# Pi3-Motherboard.net
KiCad netlist of a schematic drawn in EAGLE
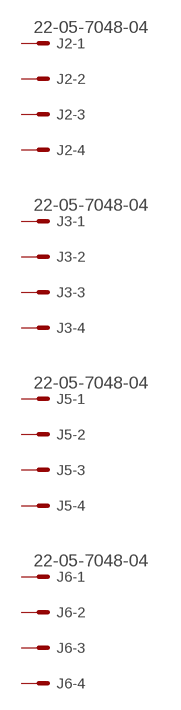
[diagram p0: schematic, sheet 1]
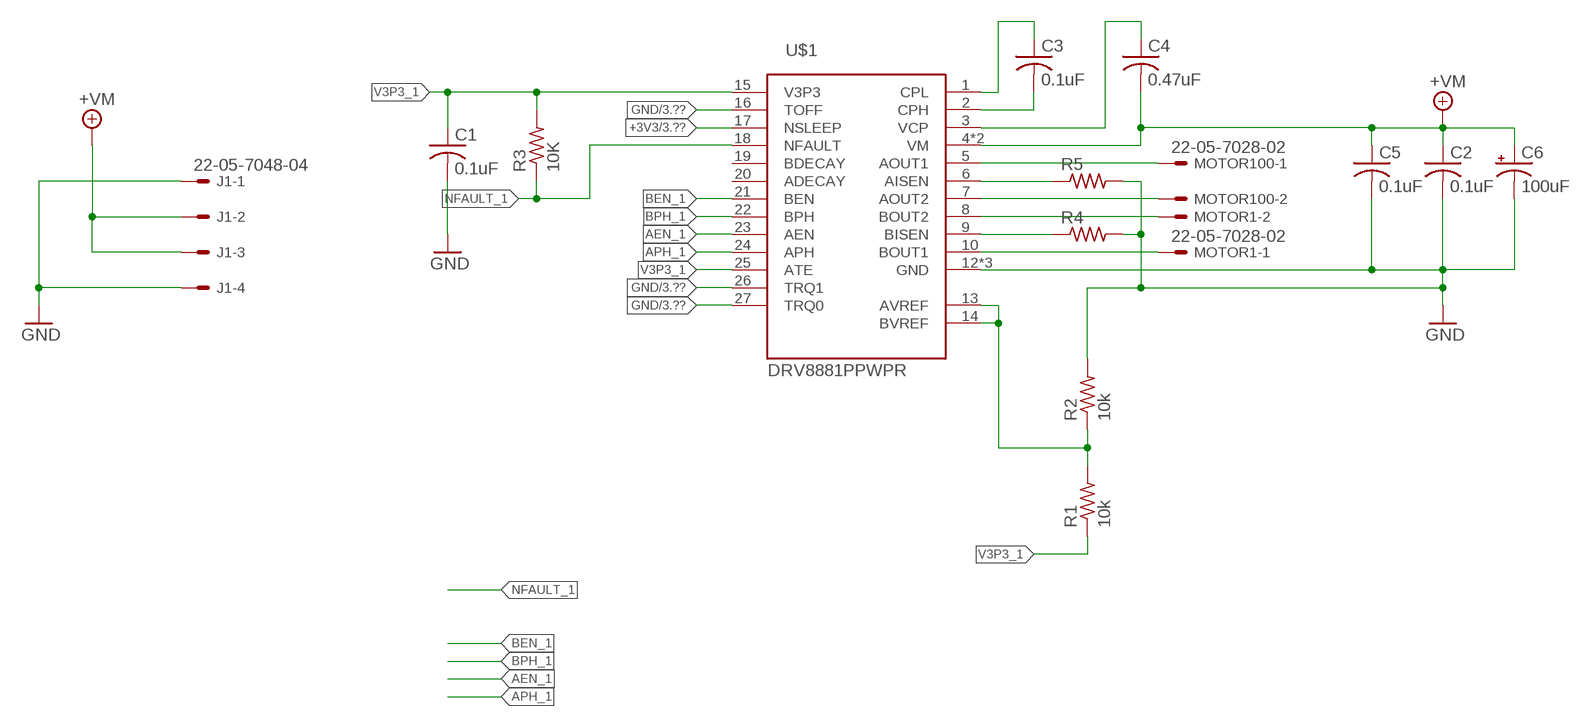
[diagram p1: schematic, sheet 2]
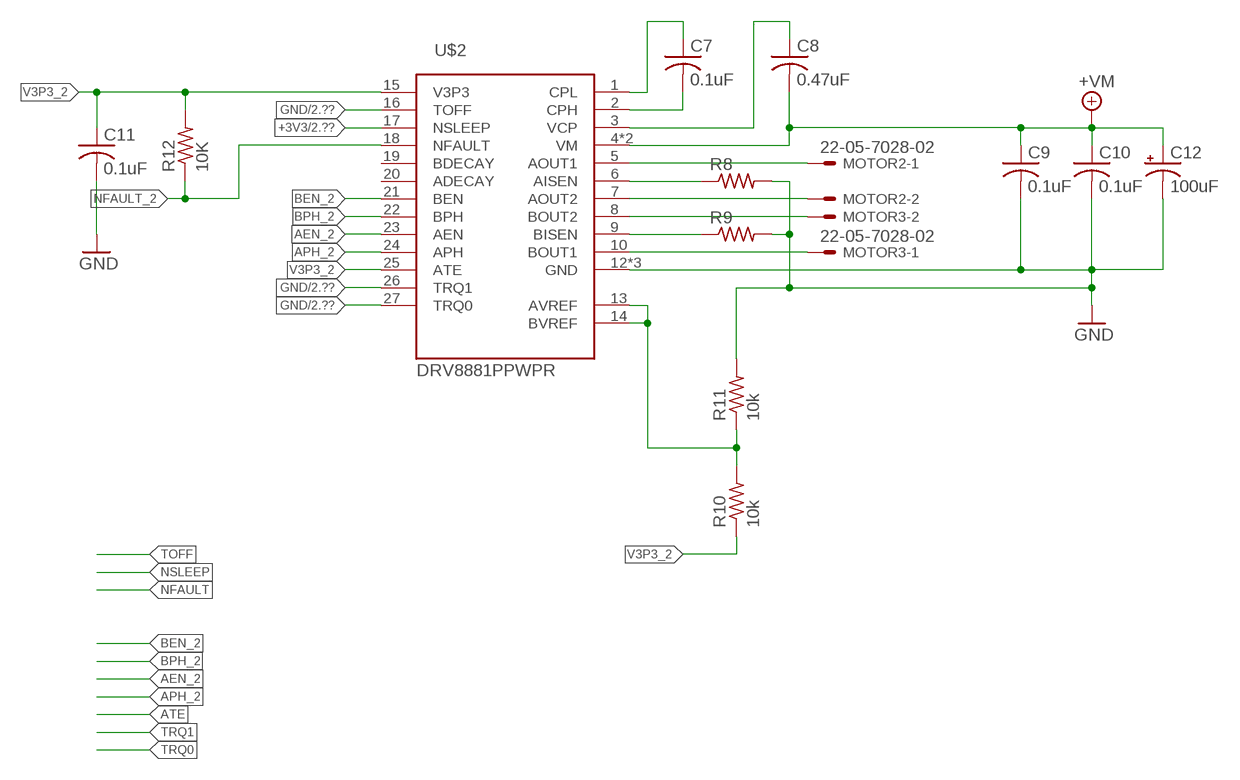
[diagram p2: schematic, sheet 3]
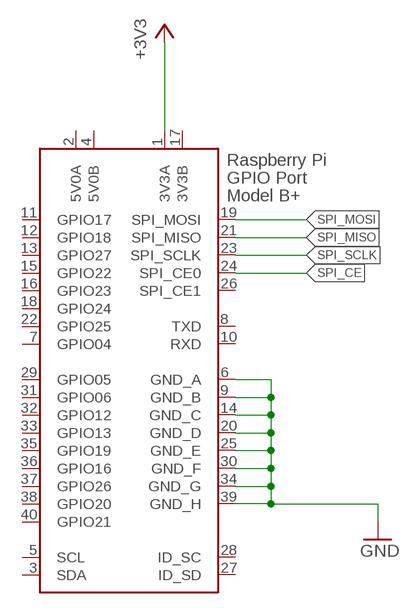
[diagram p3: schematic, sheet 4]
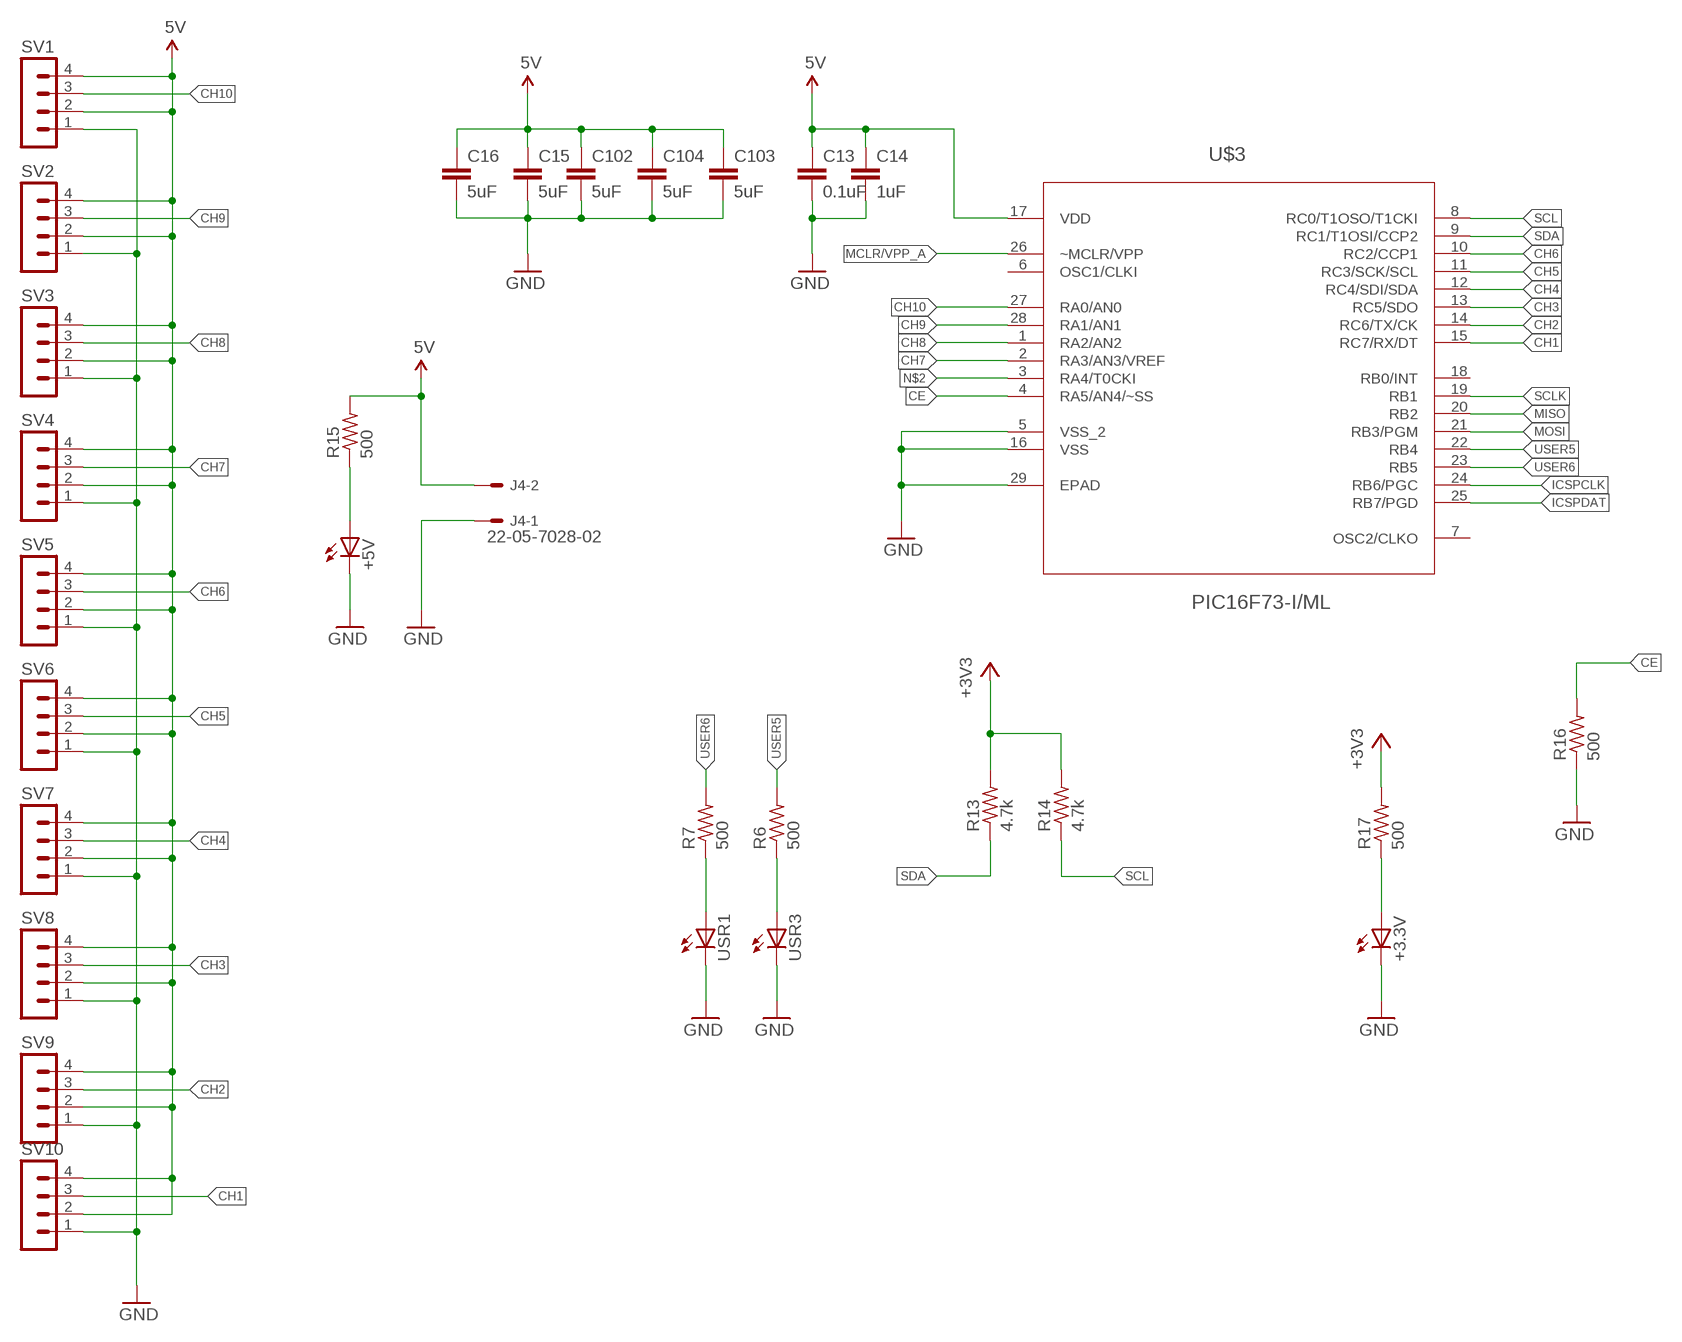
[diagram p4: schematic, sheet 5]

(export (version "E")
  (design (tool "Eeschema 10.0.6"))
  (components
    (comp (ref "X1")
      (value "RASPI_BOARD_B+#_HD")
      (footprint "eagle-import:RASPI_BOARD_B+HAT_DF")
      (libsource (lib "eagle-import") (part "RASPI_BOARD_B+#_HD"))
    )
    (comp (ref "+3.3V")
      (value "LEDCHIP-LED0603")
      (footprint "eagle-import:CHIP-LED0603")
      (libsource (lib "eagle-import") (part "LEDCHIP-LED0603"))
    )
    (comp (ref "+5V")
      (value "LEDCHIP-LED0603")
      (footprint "eagle-import:CHIP-LED0603")
      (libsource (lib "eagle-import") (part "LEDCHIP-LED0603"))
    )
    (comp (ref "C13")
      (value "0.1uF")
      (footprint "eagle-import:C0402")
      (libsource (lib "eagle-import") (part "C-EUC0402"))
    )
    (comp (ref "C14")
      (value "1uF")
      (footprint "eagle-import:C0402")
      (libsource (lib "eagle-import") (part "C-EUC0402"))
    )
    (comp (ref "C15")
      (value "5uF")
      (footprint "eagle-import:C0402")
      (libsource (lib "eagle-import") (part "C-EUC0402"))
    )
    (comp (ref "C16")
      (value "5uF")
      (footprint "eagle-import:C0402")
      (libsource (lib "eagle-import") (part "C-EUC0402"))
    )
    (comp (ref "C102")
      (value "5uF")
      (footprint "eagle-import:C0402")
      (libsource (lib "eagle-import") (part "C-EUC0402"))
    )
    (comp (ref "C103")
      (value "5uF")
      (footprint "eagle-import:C0402")
      (libsource (lib "eagle-import") (part "C-EUC0402"))
    )
    (comp (ref "C104")
      (value "5uF")
      (footprint "eagle-import:C0402")
      (libsource (lib "eagle-import") (part "C-EUC0402"))
    )
    (comp (ref "J4")
      (value "22-05-7028-02")
      (footprint "eagle-import:7395-02")
      (libsource (lib "eagle-import") (part "con-molex_22-?-0205-7028"))
    )
    (comp (ref "R6")
      (value "500")
      (footprint "eagle-import:R0402")
      (libsource (lib "eagle-import") (part "resistor_R-US_R0402"))
    )
    (comp (ref "R7")
      (value "500")
      (footprint "eagle-import:R0402")
      (libsource (lib "eagle-import") (part "resistor_R-US_R0402"))
    )
    (comp (ref "R13")
      (value "4.7k")
      (footprint "eagle-import:R0402")
      (libsource (lib "eagle-import") (part "resistor_R-US_R0402"))
    )
    (comp (ref "R14")
      (value "4.7k")
      (footprint "eagle-import:R0402")
      (libsource (lib "eagle-import") (part "resistor_R-US_R0402"))
    )
    (comp (ref "R15")
      (value "500")
      (footprint "eagle-import:R0402")
      (libsource (lib "eagle-import") (part "resistor_R-US_R0402"))
    )
    (comp (ref "R16")
      (value "500")
      (footprint "eagle-import:R0402")
      (libsource (lib "eagle-import") (part "resistor_R-US_R0402"))
    )
    (comp (ref "R17")
      (value "500")
      (footprint "eagle-import:R0402")
      (libsource (lib "eagle-import") (part "resistor_R-US_R0402"))
    )
    (comp (ref "SV1")
      (value "MA04-1")
      (footprint "eagle-import:MA04-1")
      (libsource (lib "eagle-import") (part "MA04-1"))
    )
    (comp (ref "SV2")
      (value "MA04-1")
      (footprint "eagle-import:MA04-1")
      (libsource (lib "eagle-import") (part "MA04-1"))
    )
    (comp (ref "SV3")
      (value "MA04-1")
      (footprint "eagle-import:MA04-1")
      (libsource (lib "eagle-import") (part "MA04-1"))
    )
    (comp (ref "SV4")
      (value "MA04-1")
      (footprint "eagle-import:MA04-1")
      (libsource (lib "eagle-import") (part "MA04-1"))
    )
    (comp (ref "SV5")
      (value "MA04-1")
      (footprint "eagle-import:MA04-1")
      (libsource (lib "eagle-import") (part "MA04-1"))
    )
    (comp (ref "SV6")
      (value "MA04-1")
      (footprint "eagle-import:MA04-1")
      (libsource (lib "eagle-import") (part "MA04-1"))
    )
    (comp (ref "SV7")
      (value "MA04-1")
      (footprint "eagle-import:MA04-1")
      (libsource (lib "eagle-import") (part "MA04-1"))
    )
    (comp (ref "SV8")
      (value "MA04-1")
      (footprint "eagle-import:MA04-1")
      (libsource (lib "eagle-import") (part "MA04-1"))
    )
    (comp (ref "SV9")
      (value "MA04-1")
      (footprint "eagle-import:MA04-1")
      (libsource (lib "eagle-import") (part "MA04-1"))
    )
    (comp (ref "SV10")
      (value "MA04-1")
      (footprint "eagle-import:MA04-1")
      (libsource (lib "eagle-import") (part "MA04-1"))
    )
    (comp (ref "U$3")
      (value "PIC16F73-I/ML")
      (footprint "eagle-import:QFN65P600X600X100-28N")
      (libsource (lib "eagle-import") (part "PIC16F73-I/ML"))
    )
    (comp (ref "USR1")
      (value "LEDCHIP-LED0603")
      (footprint "eagle-import:CHIP-LED0603")
      (libsource (lib "eagle-import") (part "LEDCHIP-LED0603"))
    )
    (comp (ref "USR3")
      (value "LEDCHIP-LED0603")
      (footprint "eagle-import:CHIP-LED0603")
      (libsource (lib "eagle-import") (part "LEDCHIP-LED0603"))
    )
    (comp (ref "J2")
      (value "22-05-7048-04")
      (footprint "eagle-import:7395-04")
      (libsource (lib "eagle-import") (part "22-?-0405-7048"))
    )
    (comp (ref "J3")
      (value "22-05-7048-04")
      (footprint "eagle-import:7395-04")
      (libsource (lib "eagle-import") (part "22-?-0405-7048"))
    )
    (comp (ref "J5")
      (value "22-05-7048-04")
      (footprint "eagle-import:7395-04")
      (libsource (lib "eagle-import") (part "22-?-0405-7048"))
    )
    (comp (ref "J6")
      (value "22-05-7048-04")
      (footprint "eagle-import:7395-04")
      (libsource (lib "eagle-import") (part "22-?-0405-7048"))
    )
    (comp (ref "C1")
      (value "0.1uF")
      (footprint "eagle-import:C0402")
      (libsource (lib "eagle-import") (part "C-USC0402"))
    )
    (comp (ref "C2")
      (value "0.1uF")
      (footprint "eagle-import:C0402")
      (libsource (lib "eagle-import") (part "C-USC0402"))
    )
    (comp (ref "C3")
      (value "0.1uF")
      (footprint "eagle-import:C0402")
      (libsource (lib "eagle-import") (part "C-USC0402"))
    )
    (comp (ref "C4")
      (value "0.47uF")
      (footprint "eagle-import:C0402")
      (libsource (lib "eagle-import") (part "C-USC0402"))
    )
    (comp (ref "C5")
      (value "0.1uF")
      (footprint "eagle-import:C0402")
      (libsource (lib "eagle-import") (part "C-USC0402"))
    )
    (comp (ref "C6")
      (value "100uF")
      (footprint "eagle-import:EIA7343")
      (libsource (lib "eagle-import") (part "100UF-10V-10%(TANT)"))
    )
    (comp (ref "J1")
      (value "22-05-7048-04")
      (footprint "eagle-import:7395-04")
      (libsource (lib "eagle-import") (part "22-?-0405-7048"))
    )
    (comp (ref "MOTOR1")
      (value "22-05-7028-02")
      (footprint "eagle-import:7395-02")
      (libsource (lib "eagle-import") (part "22-?-0205-7028"))
    )
    (comp (ref "MOTOR100")
      (value "22-05-7028-02")
      (footprint "eagle-import:7395-02")
      (libsource (lib "eagle-import") (part "22-?-0205-7028"))
    )
    (comp (ref "R1")
      (value "10k")
      (footprint "eagle-import:R0402")
      (libsource (lib "eagle-import") (part "R-US_R0402"))
    )
    (comp (ref "R2")
      (value "10k")
      (footprint "eagle-import:R0402")
      (libsource (lib "eagle-import") (part "R-US_R0402"))
    )
    (comp (ref "R3")
      (value "10K")
      (footprint "eagle-import:R1206")
      (libsource (lib "eagle-import") (part "R-US_R1206"))
    )
    (comp (ref "R4")
      (value "R-US_R1206")
      (footprint "eagle-import:R1206")
      (libsource (lib "eagle-import") (part "R-US_R1206"))
    )
    (comp (ref "R5")
      (value "R-US_R1206")
      (footprint "eagle-import:R1206")
      (libsource (lib "eagle-import") (part "R-US_R1206"))
    )
    (comp (ref "U$1")
      (value "DRV8881PPWPR")
      (footprint "eagle-import:TSSOP-28")
      (libsource (lib "eagle-import") (part "DRV8881PPWPR"))
    )
    (comp (ref "C7")
      (value "0.1uF")
      (footprint "eagle-import:C0402")
      (libsource (lib "eagle-import") (part "C-USC0402"))
    )
    (comp (ref "C8")
      (value "0.47uF")
      (footprint "eagle-import:C0402")
      (libsource (lib "eagle-import") (part "C-USC0402"))
    )
    (comp (ref "C9")
      (value "0.1uF")
      (footprint "eagle-import:C0402")
      (libsource (lib "eagle-import") (part "C-USC0402"))
    )
    (comp (ref "C10")
      (value "0.1uF")
      (footprint "eagle-import:C0402")
      (libsource (lib "eagle-import") (part "C-USC0402"))
    )
    (comp (ref "C11")
      (value "0.1uF")
      (footprint "eagle-import:C0402")
      (libsource (lib "eagle-import") (part "C-USC0402"))
    )
    (comp (ref "C12")
      (value "100uF")
      (footprint "eagle-import:EIA7343")
      (libsource (lib "eagle-import") (part "100UF-10V-10%(TANT)"))
    )
    (comp (ref "MOTOR2")
      (value "22-05-7028-02")
      (footprint "eagle-import:7395-02")
      (libsource (lib "eagle-import") (part "22-?-0205-7028"))
    )
    (comp (ref "MOTOR3")
      (value "22-05-7028-02")
      (footprint "eagle-import:7395-02")
      (libsource (lib "eagle-import") (part "22-?-0205-7028"))
    )
    (comp (ref "R8")
      (value "R-US_R1206")
      (footprint "eagle-import:R1206")
      (libsource (lib "eagle-import") (part "R-US_R1206"))
    )
    (comp (ref "R9")
      (value "R-US_R1206")
      (footprint "eagle-import:R1206")
      (libsource (lib "eagle-import") (part "R-US_R1206"))
    )
    (comp (ref "R10")
      (value "10k")
      (footprint "eagle-import:R0402")
      (libsource (lib "eagle-import") (part "R-US_R0402"))
    )
    (comp (ref "R11")
      (value "10k")
      (footprint "eagle-import:R0402")
      (libsource (lib "eagle-import") (part "R-US_R0402"))
    )
    (comp (ref "R12")
      (value "10K")
      (footprint "eagle-import:R1206")
      (libsource (lib "eagle-import") (part "R-US_R1206"))
    )
    (comp (ref "U$2")
      (value "DRV8881PPWPR")
      (footprint "eagle-import:TSSOP-28")
      (libsource (lib "eagle-import") (part "DRV8881PPWPR"))
    )
  )
  (nets
    (net (code "1") (name "+3V3") (class "Default")
      (node (ref "R13") (pin "2") (pinfunction "2_2") (pintype "passive"))
      (node (ref "R14") (pin "2") (pinfunction "2_2") (pintype "passive"))
      (node (ref "R17") (pin "2") (pinfunction "2_2") (pintype "passive"))
      (node (ref "U$1") (pin "17") (pinfunction "NSLEEP_17") (pintype "bidirectional"))
      (node (ref "U$2") (pin "17") (pinfunction "NSLEEP_17") (pintype "bidirectional"))
      (node (ref "X1") (pin "1") (pinfunction "3V3A_1") (pintype "power_in"))
    )
    (net (code "2") (name "+7V") (class "Default")
      (node (ref "C10") (pin "1") (pinfunction "1_1") (pintype "passive"))
      (node (ref "C12") (pin "A") (pinfunction "+_A") (pintype "passive"))
      (node (ref "C2") (pin "1") (pinfunction "1_1") (pintype "passive"))
      (node (ref "C4") (pin "2") (pinfunction "2_2") (pintype "passive"))
      (node (ref "C5") (pin "1") (pinfunction "1_1") (pintype "passive"))
      (node (ref "C6") (pin "A") (pinfunction "+_A") (pintype "passive"))
      (node (ref "C8") (pin "2") (pinfunction "2_2") (pintype "passive"))
      (node (ref "C9") (pin "1") (pinfunction "1_1") (pintype "passive"))
      (node (ref "J1") (pin "2") (pinfunction "S_2") (pintype "passive"))
      (node (ref "J1") (pin "3") (pinfunction "S_3") (pintype "passive"))
      (node (ref "U$1") (pin "11") (pinfunction "VM_11") (pintype "bidirectional"))
      (node (ref "U$1") (pin "4") (pinfunction "VM_4") (pintype "bidirectional"))
      (node (ref "U$2") (pin "11") (pinfunction "VM_11") (pintype "bidirectional"))
      (node (ref "U$2") (pin "4") (pinfunction "VM_4") (pintype "bidirectional"))
    )
    (net (code "3") (name "3V3B") (class "Default")
      (node (ref "X1") (pin "17") (pinfunction "3V3B_17") (pintype "power_in"))
    )
    (net (code "4") (name "5V") (class "Default")
      (node (ref "C102") (pin "1") (pinfunction "1_1") (pintype "passive"))
      (node (ref "C103") (pin "1") (pinfunction "1_1") (pintype "passive"))
      (node (ref "C104") (pin "1") (pinfunction "1_1") (pintype "passive"))
      (node (ref "C13") (pin "1") (pinfunction "1_1") (pintype "passive"))
      (node (ref "C14") (pin "1") (pinfunction "1_1") (pintype "passive"))
      (node (ref "C15") (pin "1") (pinfunction "1_1") (pintype "passive"))
      (node (ref "C16") (pin "1") (pinfunction "1_1") (pintype "passive"))
      (node (ref "J4") (pin "2") (pinfunction "S_2") (pintype "passive"))
      (node (ref "R15") (pin "2") (pinfunction "2_2") (pintype "passive"))
      (node (ref "SV1") (pin "2") (pinfunction "2_2") (pintype "passive"))
      (node (ref "SV1") (pin "4") (pinfunction "4_4") (pintype "passive"))
      (node (ref "SV10") (pin "2") (pinfunction "2_2") (pintype "passive"))
      (node (ref "SV10") (pin "4") (pinfunction "4_4") (pintype "passive"))
      (node (ref "SV2") (pin "2") (pinfunction "2_2") (pintype "passive"))
      (node (ref "SV2") (pin "4") (pinfunction "4_4") (pintype "passive"))
      (node (ref "SV3") (pin "2") (pinfunction "2_2") (pintype "passive"))
      (node (ref "SV3") (pin "4") (pinfunction "4_4") (pintype "passive"))
      (node (ref "SV4") (pin "2") (pinfunction "2_2") (pintype "passive"))
      (node (ref "SV4") (pin "4") (pinfunction "4_4") (pintype "passive"))
      (node (ref "SV5") (pin "2") (pinfunction "2_2") (pintype "passive"))
      (node (ref "SV5") (pin "4") (pinfunction "4_4") (pintype "passive"))
      (node (ref "SV6") (pin "2") (pinfunction "2_2") (pintype "passive"))
      (node (ref "SV6") (pin "4") (pinfunction "4_4") (pintype "passive"))
      (node (ref "SV7") (pin "2") (pinfunction "2_2") (pintype "passive"))
      (node (ref "SV7") (pin "4") (pinfunction "4_4") (pintype "passive"))
      (node (ref "SV8") (pin "2") (pinfunction "2_2") (pintype "passive"))
      (node (ref "SV8") (pin "4") (pinfunction "4_4") (pintype "passive"))
      (node (ref "SV9") (pin "2") (pinfunction "2_2") (pintype "passive"))
      (node (ref "SV9") (pin "4") (pinfunction "4_4") (pintype "passive"))
      (node (ref "U$3") (pin "17") (pinfunction "VDD_17") (pintype "power_in"))
    )
    (net (code "5") (name "5V0A") (class "Default")
      (node (ref "X1") (pin "2") (pinfunction "5V0A_2") (pintype "power_in"))
    )
    (net (code "6") (name "5V0B") (class "Default")
      (node (ref "X1") (pin "4") (pinfunction "5V0B_4") (pintype "power_in"))
    )
    (net (code "7") (name "AEN_1") (class "Default")
      (node (ref "U$1") (pin "23") (pinfunction "AEN_23") (pintype "bidirectional"))
    )
    (net (code "8") (name "AEN_2") (class "Default")
      (node (ref "U$2") (pin "23") (pinfunction "AEN_23") (pintype "bidirectional"))
    )
    (net (code "9") (name "APH_1") (class "Default")
      (node (ref "U$1") (pin "24") (pinfunction "APH_24") (pintype "bidirectional"))
    )
    (net (code "10") (name "APH_2") (class "Default")
      (node (ref "U$2") (pin "24") (pinfunction "APH_24") (pintype "bidirectional"))
    )
    (net (code "12") (name "BEN_1") (class "Default")
      (node (ref "U$1") (pin "21") (pinfunction "BEN_21") (pintype "bidirectional"))
    )
    (net (code "13") (name "BEN_2") (class "Default")
      (node (ref "U$2") (pin "21") (pinfunction "BEN_21") (pintype "bidirectional"))
    )
    (net (code "14") (name "BPH_1") (class "Default")
      (node (ref "U$1") (pin "22") (pinfunction "BPH_22") (pintype "bidirectional"))
    )
    (net (code "15") (name "BPH_2") (class "Default")
      (node (ref "U$2") (pin "22") (pinfunction "BPH_22") (pintype "bidirectional"))
    )
    (net (code "16") (name "CE") (class "Default")
      (node (ref "R16") (pin "2") (pinfunction "2_2") (pintype "passive"))
      (node (ref "U$3") (pin "4") (pinfunction "RA5/AN4/~{SS}_4") (pintype "bidirectional"))
    )
    (net (code "17") (name "CH1") (class "Default")
      (node (ref "SV10") (pin "3") (pinfunction "3_3") (pintype "passive"))
      (node (ref "U$3") (pin "15") (pinfunction "RC7/RX/DT_15") (pintype "bidirectional"))
    )
    (net (code "18") (name "CH2") (class "Default")
      (node (ref "SV9") (pin "3") (pinfunction "3_3") (pintype "passive"))
      (node (ref "U$3") (pin "14") (pinfunction "RC6/TX/CK_14") (pintype "bidirectional"))
    )
    (net (code "19") (name "CH3") (class "Default")
      (node (ref "SV8") (pin "3") (pinfunction "3_3") (pintype "passive"))
      (node (ref "U$3") (pin "13") (pinfunction "RC5/SDO_13") (pintype "bidirectional"))
    )
    (net (code "20") (name "CH4") (class "Default")
      (node (ref "SV7") (pin "3") (pinfunction "3_3") (pintype "passive"))
      (node (ref "U$3") (pin "12") (pinfunction "RC4/SDI/SDA_12") (pintype "bidirectional"))
    )
    (net (code "21") (name "CH5") (class "Default")
      (node (ref "SV6") (pin "3") (pinfunction "3_3") (pintype "passive"))
      (node (ref "U$3") (pin "11") (pinfunction "RC3/SCK/SCL_11") (pintype "bidirectional"))
    )
    (net (code "22") (name "CH6") (class "Default")
      (node (ref "SV5") (pin "3") (pinfunction "3_3") (pintype "passive"))
      (node (ref "U$3") (pin "10") (pinfunction "RC2/CCP1_10") (pintype "bidirectional"))
    )
    (net (code "23") (name "CH7") (class "Default")
      (node (ref "SV4") (pin "3") (pinfunction "3_3") (pintype "passive"))
      (node (ref "U$3") (pin "2") (pinfunction "RA3/AN3/VREF_2") (pintype "bidirectional"))
    )
    (net (code "24") (name "CH8") (class "Default")
      (node (ref "SV3") (pin "3") (pinfunction "3_3") (pintype "passive"))
      (node (ref "U$3") (pin "1") (pinfunction "RA2/AN2_1") (pintype "bidirectional"))
    )
    (net (code "25") (name "CH9") (class "Default")
      (node (ref "SV2") (pin "3") (pinfunction "3_3") (pintype "passive"))
      (node (ref "U$3") (pin "28") (pinfunction "RA1/AN1_28") (pintype "bidirectional"))
    )
    (net (code "26") (name "CH10") (class "Default")
      (node (ref "SV1") (pin "3") (pinfunction "3_3") (pintype "passive"))
      (node (ref "U$3") (pin "27") (pinfunction "RA0/AN0_27") (pintype "bidirectional"))
    )
    (net (code "27") (name "GND") (class "Default")
      (node (ref "+3.3V") (pin "C") (pinfunction "C_C") (pintype "passive"))
      (node (ref "+5V") (pin "C") (pinfunction "C_C") (pintype "passive"))
      (node (ref "C1") (pin "2") (pinfunction "2_2") (pintype "passive"))
      (node (ref "C10") (pin "2") (pinfunction "2_2") (pintype "passive"))
      (node (ref "C102") (pin "2") (pinfunction "2_2") (pintype "passive"))
      (node (ref "C103") (pin "2") (pinfunction "2_2") (pintype "passive"))
      (node (ref "C104") (pin "2") (pinfunction "2_2") (pintype "passive"))
      (node (ref "C11") (pin "2") (pinfunction "2_2") (pintype "passive"))
      (node (ref "C12") (pin "C") (pinfunction "-_C") (pintype "passive"))
      (node (ref "C13") (pin "2") (pinfunction "2_2") (pintype "passive"))
      (node (ref "C14") (pin "2") (pinfunction "2_2") (pintype "passive"))
      (node (ref "C15") (pin "2") (pinfunction "2_2") (pintype "passive"))
      (node (ref "C16") (pin "2") (pinfunction "2_2") (pintype "passive"))
      (node (ref "C2") (pin "2") (pinfunction "2_2") (pintype "passive"))
      (node (ref "C5") (pin "2") (pinfunction "2_2") (pintype "passive"))
      (node (ref "C6") (pin "C") (pinfunction "-_C") (pintype "passive"))
      (node (ref "C9") (pin "2") (pinfunction "2_2") (pintype "passive"))
      (node (ref "J1") (pin "1") (pinfunction "S_1") (pintype "passive"))
      (node (ref "J1") (pin "4") (pinfunction "S_4") (pintype "passive"))
      (node (ref "J4") (pin "1") (pinfunction "S_1") (pintype "passive"))
      (node (ref "R11") (pin "2") (pinfunction "2_2") (pintype "passive"))
      (node (ref "R16") (pin "1") (pinfunction "1_1") (pintype "passive"))
      (node (ref "R2") (pin "2") (pinfunction "2_2") (pintype "passive"))
      (node (ref "R4") (pin "2") (pinfunction "2_2") (pintype "passive"))
      (node (ref "R5") (pin "2") (pinfunction "2_2") (pintype "passive"))
      (node (ref "R8") (pin "2") (pinfunction "2_2") (pintype "passive"))
      (node (ref "R9") (pin "2") (pinfunction "2_2") (pintype "passive"))
      (node (ref "SV1") (pin "1") (pinfunction "1_1") (pintype "passive"))
      (node (ref "SV10") (pin "1") (pinfunction "1_1") (pintype "passive"))
      (node (ref "SV2") (pin "1") (pinfunction "1_1") (pintype "passive"))
      (node (ref "SV3") (pin "1") (pinfunction "1_1") (pintype "passive"))
      (node (ref "SV4") (pin "1") (pinfunction "1_1") (pintype "passive"))
      (node (ref "SV5") (pin "1") (pinfunction "1_1") (pintype "passive"))
      (node (ref "SV6") (pin "1") (pinfunction "1_1") (pintype "passive"))
      (node (ref "SV7") (pin "1") (pinfunction "1_1") (pintype "passive"))
      (node (ref "SV8") (pin "1") (pinfunction "1_1") (pintype "passive"))
      (node (ref "SV9") (pin "1") (pinfunction "1_1") (pintype "passive"))
      (node (ref "U$1") (pin "12") (pinfunction "GND_12") (pintype "bidirectional"))
      (node (ref "U$1") (pin "16") (pinfunction "TOFF_16") (pintype "bidirectional"))
      (node (ref "U$1") (pin "26") (pinfunction "TRQ1_26") (pintype "bidirectional"))
      (node (ref "U$1") (pin "27") (pinfunction "TRQ0_27") (pintype "bidirectional"))
      (node (ref "U$1") (pin "28") (pinfunction "GND_28") (pintype "bidirectional"))
      (node (ref "U$1") (pin "EXP") (pinfunction "GND_EXP") (pintype "bidirectional"))
      (node (ref "U$2") (pin "12") (pinfunction "GND_12") (pintype "bidirectional"))
      (node (ref "U$2") (pin "16") (pinfunction "TOFF_16") (pintype "bidirectional"))
      (node (ref "U$2") (pin "26") (pinfunction "TRQ1_26") (pintype "bidirectional"))
      (node (ref "U$2") (pin "27") (pinfunction "TRQ0_27") (pintype "bidirectional"))
      (node (ref "U$2") (pin "28") (pinfunction "GND_28") (pintype "bidirectional"))
      (node (ref "U$2") (pin "EXP") (pinfunction "GND_EXP") (pintype "bidirectional"))
      (node (ref "U$3") (pin "16") (pinfunction "VSS_16") (pintype "power_in"))
      (node (ref "U$3") (pin "29") (pinfunction "EPAD_29") (pintype "passive"))
      (node (ref "U$3") (pin "5") (pinfunction "VSS_2_5") (pintype "power_in"))
      (node (ref "USR1") (pin "C") (pinfunction "C_C") (pintype "passive"))
      (node (ref "USR3") (pin "C") (pinfunction "C_C") (pintype "passive"))
      (node (ref "X1") (pin "14") (pinfunction "GND_C_14") (pintype "power_in"))
      (node (ref "X1") (pin "20") (pinfunction "GND_D_20") (pintype "power_in"))
      (node (ref "X1") (pin "25") (pinfunction "GND_E_25") (pintype "power_in"))
      (node (ref "X1") (pin "30") (pinfunction "GND_F_30") (pintype "power_in"))
      (node (ref "X1") (pin "34") (pinfunction "GND_G_34") (pintype "power_in"))
      (node (ref "X1") (pin "39") (pinfunction "GND_H_39") (pintype "power_in"))
      (node (ref "X1") (pin "6") (pinfunction "GND_A_6") (pintype "power_in"))
      (node (ref "X1") (pin "9") (pinfunction "GND_B_9") (pintype "power_in"))
    )
    (net (code "28") (name "ICSPCLK") (class "Default")
      (node (ref "U$3") (pin "24") (pinfunction "RB6/PGC_24") (pintype "bidirectional"))
    )
    (net (code "29") (name "ICSPDAT") (class "Default")
      (node (ref "U$3") (pin "25") (pinfunction "RB7/PGD_25") (pintype "bidirectional"))
    )
    (net (code "30") (name "MCLR{slash}VPP_A") (class "Default")
      (node (ref "U$3") (pin "26") (pinfunction "~{MCLR/VPP}_26") (pintype "input"))
    )
    (net (code "31") (name "MISO") (class "Default")
      (node (ref "U$3") (pin "20") (pinfunction "RB2_20") (pintype "bidirectional"))
    )
    (net (code "32") (name "MOSI") (class "Default")
      (node (ref "U$3") (pin "21") (pinfunction "RB3/PGM_21") (pintype "bidirectional"))
    )
    (net (code "33") (name "N$2") (class "Default")
      (node (ref "R5") (pin "1") (pinfunction "1_1") (pintype "passive"))
      (node (ref "U$1") (pin "6") (pinfunction "AISEN_6") (pintype "bidirectional"))
      (node (ref "U$3") (pin "3") (pinfunction "RA4/T0CKI_3") (pintype "bidirectional"))
    )
    (net (code "35") (name "NFAULT_1") (class "Default")
      (node (ref "R3") (pin "1") (pinfunction "1_1") (pintype "passive"))
      (node (ref "U$1") (pin "18") (pinfunction "NFAULT_18") (pintype "bidirectional"))
    )
    (net (code "36") (name "NFAULT_2") (class "Default")
      (node (ref "R12") (pin "1") (pinfunction "1_1") (pintype "passive"))
      (node (ref "U$2") (pin "18") (pinfunction "NFAULT_18") (pintype "bidirectional"))
    )
    (net (code "38") (name "Net-(+3.3V-PadA)") (class "Default")
      (node (ref "+3.3V") (pin "A") (pinfunction "A_A") (pintype "passive"))
      (node (ref "R17") (pin "1") (pinfunction "1_1") (pintype "passive"))
    )
    (net (code "39") (name "Net-(+5V-PadA)") (class "Default")
      (node (ref "+5V") (pin "A") (pinfunction "A_A") (pintype "passive"))
      (node (ref "R15") (pin "1") (pinfunction "1_1") (pintype "passive"))
    )
    (net (code "40") (name "Net-(MOTOR1A-S)") (class "Default")
      (node (ref "MOTOR1") (pin "1") (pinfunction "S_1") (pintype "passive"))
      (node (ref "U$1") (pin "10") (pinfunction "BOUT1_10") (pintype "bidirectional"))
    )
    (net (code "41") (name "Net-(MOTOR1B-S)") (class "Default")
      (node (ref "MOTOR1") (pin "2") (pinfunction "S_2") (pintype "passive"))
      (node (ref "U$1") (pin "8") (pinfunction "BOUT2_8") (pintype "bidirectional"))
    )
    (net (code "42") (name "Net-(MOTOR2A-S)") (class "Default")
      (node (ref "MOTOR2") (pin "1") (pinfunction "S_1") (pintype "passive"))
      (node (ref "U$2") (pin "5") (pinfunction "AOUT1_5") (pintype "bidirectional"))
    )
    (net (code "43") (name "Net-(MOTOR2B-S)") (class "Default")
      (node (ref "MOTOR2") (pin "2") (pinfunction "S_2") (pintype "passive"))
      (node (ref "U$2") (pin "7") (pinfunction "AOUT2_7") (pintype "bidirectional"))
    )
    (net (code "44") (name "Net-(MOTOR3A-S)") (class "Default")
      (node (ref "MOTOR3") (pin "1") (pinfunction "S_1") (pintype "passive"))
      (node (ref "U$2") (pin "10") (pinfunction "BOUT1_10") (pintype "bidirectional"))
    )
    (net (code "45") (name "Net-(MOTOR3B-S)") (class "Default")
      (node (ref "MOTOR3") (pin "2") (pinfunction "S_2") (pintype "passive"))
      (node (ref "U$2") (pin "8") (pinfunction "BOUT2_8") (pintype "bidirectional"))
    )
    (net (code "46") (name "Net-(MOTOR100A-S)") (class "Default")
      (node (ref "MOTOR100") (pin "1") (pinfunction "S_1") (pintype "passive"))
      (node (ref "U$1") (pin "5") (pinfunction "AOUT1_5") (pintype "bidirectional"))
    )
    (net (code "47") (name "Net-(MOTOR100B-S)") (class "Default")
      (node (ref "MOTOR100") (pin "2") (pinfunction "S_2") (pintype "passive"))
      (node (ref "U$1") (pin "7") (pinfunction "AOUT2_7") (pintype "bidirectional"))
    )
    (net (code "48") (name "Net-(R6-Pad1)") (class "Default")
      (node (ref "R6") (pin "1") (pinfunction "1_1") (pintype "passive"))
      (node (ref "USR3") (pin "A") (pinfunction "A_A") (pintype "passive"))
    )
    (net (code "49") (name "Net-(R7-Pad1)") (class "Default")
      (node (ref "R7") (pin "1") (pinfunction "1_1") (pintype "passive"))
      (node (ref "USR1") (pin "A") (pinfunction "A_A") (pintype "passive"))
    )
    (net (code "50") (name "Net-(U$1-AVREF)") (class "Default")
      (node (ref "R1") (pin "2") (pinfunction "2_2") (pintype "passive"))
      (node (ref "R2") (pin "1") (pinfunction "1_1") (pintype "passive"))
      (node (ref "U$1") (pin "13") (pinfunction "AVREF_13") (pintype "bidirectional"))
      (node (ref "U$1") (pin "14") (pinfunction "BVREF_14") (pintype "bidirectional"))
    )
    (net (code "51") (name "Net-(U$1-BISEN)") (class "Default")
      (node (ref "R4") (pin "1") (pinfunction "1_1") (pintype "passive"))
      (node (ref "U$1") (pin "9") (pinfunction "BISEN_9") (pintype "bidirectional"))
    )
    (net (code "52") (name "Net-(U$1-CPH)") (class "Default")
      (node (ref "C3") (pin "2") (pinfunction "2_2") (pintype "passive"))
      (node (ref "U$1") (pin "2") (pinfunction "CPH_2") (pintype "bidirectional"))
    )
    (net (code "53") (name "Net-(U$1-CPL)") (class "Default")
      (node (ref "C3") (pin "1") (pinfunction "1_1") (pintype "passive"))
      (node (ref "U$1") (pin "1") (pinfunction "CPL_1") (pintype "bidirectional"))
    )
    (net (code "54") (name "Net-(U$1-VCP)") (class "Default")
      (node (ref "C4") (pin "1") (pinfunction "1_1") (pintype "passive"))
      (node (ref "U$1") (pin "3") (pinfunction "VCP_3") (pintype "bidirectional"))
    )
    (net (code "55") (name "Net-(U$2-AISEN)") (class "Default")
      (node (ref "R8") (pin "1") (pinfunction "1_1") (pintype "passive"))
      (node (ref "U$2") (pin "6") (pinfunction "AISEN_6") (pintype "bidirectional"))
    )
    (net (code "56") (name "Net-(U$2-AVREF)") (class "Default")
      (node (ref "R10") (pin "2") (pinfunction "2_2") (pintype "passive"))
      (node (ref "R11") (pin "1") (pinfunction "1_1") (pintype "passive"))
      (node (ref "U$2") (pin "13") (pinfunction "AVREF_13") (pintype "bidirectional"))
      (node (ref "U$2") (pin "14") (pinfunction "BVREF_14") (pintype "bidirectional"))
    )
    (net (code "57") (name "Net-(U$2-BISEN)") (class "Default")
      (node (ref "R9") (pin "1") (pinfunction "1_1") (pintype "passive"))
      (node (ref "U$2") (pin "9") (pinfunction "BISEN_9") (pintype "bidirectional"))
    )
    (net (code "58") (name "Net-(U$2-CPH)") (class "Default")
      (node (ref "C7") (pin "2") (pinfunction "2_2") (pintype "passive"))
      (node (ref "U$2") (pin "2") (pinfunction "CPH_2") (pintype "bidirectional"))
    )
    (net (code "59") (name "Net-(U$2-CPL)") (class "Default")
      (node (ref "C7") (pin "1") (pinfunction "1_1") (pintype "passive"))
      (node (ref "U$2") (pin "1") (pinfunction "CPL_1") (pintype "bidirectional"))
    )
    (net (code "60") (name "Net-(U$2-VCP)") (class "Default")
      (node (ref "C8") (pin "1") (pinfunction "1_1") (pintype "passive"))
      (node (ref "U$2") (pin "3") (pinfunction "VCP_3") (pintype "bidirectional"))
    )
    (net (code "61") (name "SCL") (class "Default")
      (node (ref "R14") (pin "1") (pinfunction "1_1") (pintype "passive"))
      (node (ref "U$3") (pin "8") (pinfunction "RC0/T1OSO/T1CKI_8") (pintype "bidirectional"))
    )
    (net (code "62") (name "SCLK") (class "Default")
      (node (ref "U$3") (pin "19") (pinfunction "RB1_19") (pintype "bidirectional"))
    )
    (net (code "63") (name "SDA") (class "Default")
      (node (ref "R13") (pin "1") (pinfunction "1_1") (pintype "passive"))
      (node (ref "U$3") (pin "9") (pinfunction "RC1/T1OSI/CCP2_9") (pintype "bidirectional"))
    )
    (net (code "64") (name "SPI_CE") (class "Default")
      (node (ref "X1") (pin "24") (pinfunction "SPI_CE0_24") (pintype "bidirectional"))
    )
    (net (code "65") (name "SPI_MISO") (class "Default")
      (node (ref "X1") (pin "21") (pinfunction "SPI_MISO_21") (pintype "bidirectional"))
    )
    (net (code "66") (name "SPI_MOSI") (class "Default")
      (node (ref "X1") (pin "19") (pinfunction "SPI_MOSI_19") (pintype "bidirectional"))
    )
    (net (code "67") (name "SPI_SCLK") (class "Default")
      (node (ref "X1") (pin "23") (pinfunction "SPI_SCLK_23") (pintype "bidirectional"))
    )
    (net (code "71") (name "USER5") (class "Default")
      (node (ref "R6") (pin "2") (pinfunction "2_2") (pintype "passive"))
      (node (ref "U$3") (pin "22") (pinfunction "RB4_22") (pintype "bidirectional"))
    )
    (net (code "72") (name "USER6") (class "Default")
      (node (ref "R7") (pin "2") (pinfunction "2_2") (pintype "passive"))
      (node (ref "U$3") (pin "23") (pinfunction "RB5_23") (pintype "bidirectional"))
    )
    (net (code "73") (name "V3P3_1") (class "Default")
      (node (ref "C1") (pin "1") (pinfunction "1_1") (pintype "passive"))
      (node (ref "R1") (pin "1") (pinfunction "1_1") (pintype "passive"))
      (node (ref "R3") (pin "2") (pinfunction "2_2") (pintype "passive"))
      (node (ref "U$1") (pin "15") (pinfunction "V3P3_15") (pintype "bidirectional"))
      (node (ref "U$1") (pin "25") (pinfunction "ATE_25") (pintype "bidirectional"))
    )
    (net (code "74") (name "V3P3_2") (class "Default")
      (node (ref "C11") (pin "1") (pinfunction "1_1") (pintype "passive"))
      (node (ref "R10") (pin "1") (pinfunction "1_1") (pintype "passive"))
      (node (ref "R12") (pin "2") (pinfunction "2_2") (pintype "passive"))
      (node (ref "U$2") (pin "15") (pinfunction "V3P3_15") (pintype "bidirectional"))
      (node (ref "U$2") (pin "25") (pinfunction "ATE_25") (pintype "bidirectional"))
    )
    (net (code "75") (name "unconnected-(J2A-S-Pad1)") (class "Default")
      (node (ref "J2") (pin "1") (pinfunction "S_1") (pintype "passive"))
    )
    (net (code "76") (name "unconnected-(J2B-S-Pad2)") (class "Default")
      (node (ref "J2") (pin "2") (pinfunction "S_2") (pintype "passive"))
    )
    (net (code "77") (name "unconnected-(J2C-S-Pad3)") (class "Default")
      (node (ref "J2") (pin "3") (pinfunction "S_3") (pintype "passive"))
    )
    (net (code "78") (name "unconnected-(J2D-S-Pad4)") (class "Default")
      (node (ref "J2") (pin "4") (pinfunction "S_4") (pintype "passive"))
    )
    (net (code "79") (name "unconnected-(J3A-S-Pad1)") (class "Default")
      (node (ref "J3") (pin "1") (pinfunction "S_1") (pintype "passive"))
    )
    (net (code "80") (name "unconnected-(J3B-S-Pad2)") (class "Default")
      (node (ref "J3") (pin "2") (pinfunction "S_2") (pintype "passive"))
    )
    (net (code "81") (name "unconnected-(J3C-S-Pad3)") (class "Default")
      (node (ref "J3") (pin "3") (pinfunction "S_3") (pintype "passive"))
    )
    (net (code "82") (name "unconnected-(J3D-S-Pad4)") (class "Default")
      (node (ref "J3") (pin "4") (pinfunction "S_4") (pintype "passive"))
    )
    (net (code "83") (name "unconnected-(J5A-S-Pad1)") (class "Default")
      (node (ref "J5") (pin "1") (pinfunction "S_1") (pintype "passive"))
    )
    (net (code "84") (name "unconnected-(J5B-S-Pad2)") (class "Default")
      (node (ref "J5") (pin "2") (pinfunction "S_2") (pintype "passive"))
    )
    (net (code "85") (name "unconnected-(J5C-S-Pad3)") (class "Default")
      (node (ref "J5") (pin "3") (pinfunction "S_3") (pintype "passive"))
    )
    (net (code "86") (name "unconnected-(J5D-S-Pad4)") (class "Default")
      (node (ref "J5") (pin "4") (pinfunction "S_4") (pintype "passive"))
    )
    (net (code "87") (name "unconnected-(J6A-S-Pad1)") (class "Default")
      (node (ref "J6") (pin "1") (pinfunction "S_1") (pintype "passive"))
    )
    (net (code "88") (name "unconnected-(J6B-S-Pad2)") (class "Default")
      (node (ref "J6") (pin "2") (pinfunction "S_2") (pintype "passive"))
    )
    (net (code "89") (name "unconnected-(J6C-S-Pad3)") (class "Default")
      (node (ref "J6") (pin "3") (pinfunction "S_3") (pintype "passive"))
    )
    (net (code "90") (name "unconnected-(J6D-S-Pad4)") (class "Default")
      (node (ref "J6") (pin "4") (pinfunction "S_4") (pintype "passive"))
    )
    (net (code "91") (name "unconnected-(U$1-ADECAY-Pad20)") (class "Default")
      (node (ref "U$1") (pin "20") (pinfunction "ADECAY_20") (pintype "bidirectional"))
    )
    (net (code "92") (name "unconnected-(U$1-BDECAY-Pad19)") (class "Default")
      (node (ref "U$1") (pin "19") (pinfunction "BDECAY_19") (pintype "bidirectional"))
    )
    (net (code "93") (name "unconnected-(U$2-ADECAY-Pad20)") (class "Default")
      (node (ref "U$2") (pin "20") (pinfunction "ADECAY_20") (pintype "bidirectional"))
    )
    (net (code "94") (name "unconnected-(U$2-BDECAY-Pad19)") (class "Default")
      (node (ref "U$2") (pin "19") (pinfunction "BDECAY_19") (pintype "bidirectional"))
    )
    (net (code "95") (name "unconnected-(U$3-OSC1{slash}CLKI-Pad6)") (class "Default")
      (node (ref "U$3") (pin "6") (pinfunction "OSC1/CLKI_6") (pintype "input"))
    )
    (net (code "96") (name "unconnected-(U$3-OSC2{slash}CLKO-Pad7)") (class "Default")
      (node (ref "U$3") (pin "7") (pinfunction "OSC2/CLKO_7") (pintype "output"))
    )
    (net (code "97") (name "unconnected-(U$3-RB0{slash}INT-Pad18)") (class "Default")
      (node (ref "U$3") (pin "18") (pinfunction "RB0/INT_18") (pintype "bidirectional"))
    )
    (net (code "98") (name "unconnected-(X1-GPIO04-Pad7)") (class "Default")
      (node (ref "X1") (pin "7") (pinfunction "GPIO04_7") (pintype "bidirectional"))
    )
    (net (code "99") (name "unconnected-(X1-GPIO05-Pad29)") (class "Default")
      (node (ref "X1") (pin "29") (pinfunction "GPIO05_29") (pintype "no_connect"))
    )
    (net (code "100") (name "unconnected-(X1-GPIO06-Pad31)") (class "Default")
      (node (ref "X1") (pin "31") (pinfunction "GPIO06_31") (pintype "no_connect"))
    )
    (net (code "101") (name "unconnected-(X1-GPIO12-Pad32)") (class "Default")
      (node (ref "X1") (pin "32") (pinfunction "GPIO12_32") (pintype "no_connect"))
    )
    (net (code "102") (name "unconnected-(X1-GPIO13-Pad33)") (class "Default")
      (node (ref "X1") (pin "33") (pinfunction "GPIO13_33") (pintype "no_connect"))
    )
    (net (code "103") (name "unconnected-(X1-GPIO16-Pad36)") (class "Default")
      (node (ref "X1") (pin "36") (pinfunction "GPIO16_36") (pintype "no_connect"))
    )
    (net (code "104") (name "unconnected-(X1-GPIO17-Pad11)") (class "Default")
      (node (ref "X1") (pin "11") (pinfunction "GPIO17_11") (pintype "bidirectional"))
    )
    (net (code "105") (name "unconnected-(X1-GPIO18-Pad12)") (class "Default")
      (node (ref "X1") (pin "12") (pinfunction "GPIO18_12") (pintype "bidirectional"))
    )
    (net (code "106") (name "unconnected-(X1-GPIO19-Pad35)") (class "Default")
      (node (ref "X1") (pin "35") (pinfunction "GPIO19_35") (pintype "no_connect"))
    )
    (net (code "107") (name "unconnected-(X1-GPIO20-Pad38)") (class "Default")
      (node (ref "X1") (pin "38") (pinfunction "GPIO20_38") (pintype "no_connect"))
    )
    (net (code "108") (name "unconnected-(X1-GPIO21-Pad40)") (class "Default")
      (node (ref "X1") (pin "40") (pinfunction "GPIO21_40") (pintype "no_connect"))
    )
    (net (code "109") (name "unconnected-(X1-GPIO22-Pad15)") (class "Default")
      (node (ref "X1") (pin "15") (pinfunction "GPIO22_15") (pintype "bidirectional"))
    )
    (net (code "110") (name "unconnected-(X1-GPIO23-Pad16)") (class "Default")
      (node (ref "X1") (pin "16") (pinfunction "GPIO23_16") (pintype "bidirectional"))
    )
    (net (code "111") (name "unconnected-(X1-GPIO24-Pad18)") (class "Default")
      (node (ref "X1") (pin "18") (pinfunction "GPIO24_18") (pintype "bidirectional"))
    )
    (net (code "112") (name "unconnected-(X1-GPIO25-Pad22)") (class "Default")
      (node (ref "X1") (pin "22") (pinfunction "GPIO25_22") (pintype "bidirectional"))
    )
    (net (code "113") (name "unconnected-(X1-GPIO26-Pad37)") (class "Default")
      (node (ref "X1") (pin "37") (pinfunction "GPIO26_37") (pintype "no_connect"))
    )
    (net (code "114") (name "unconnected-(X1-GPIO27-Pad13)") (class "Default")
      (node (ref "X1") (pin "13") (pinfunction "GPIO27_13") (pintype "bidirectional"))
    )
    (net (code "115") (name "unconnected-(X1-ID_SC-Pad28)") (class "Default")
      (node (ref "X1") (pin "28") (pinfunction "ID_SC_28") (pintype "no_connect"))
    )
    (net (code "116") (name "unconnected-(X1-ID_SD-Pad27)") (class "Default")
      (node (ref "X1") (pin "27") (pinfunction "ID_SD_27") (pintype "no_connect"))
    )
    (net (code "117") (name "unconnected-(X1-RXD-Pad10)") (class "Default")
      (node (ref "X1") (pin "10") (pinfunction "RXD_10") (pintype "bidirectional"))
    )
    (net (code "118") (name "unconnected-(X1-SCL-Pad5)") (class "Default")
      (node (ref "X1") (pin "5") (pinfunction "SCL_5") (pintype "bidirectional"))
    )
    (net (code "119") (name "unconnected-(X1-SDA-Pad3)") (class "Default")
      (node (ref "X1") (pin "3") (pinfunction "SDA_3") (pintype "bidirectional"))
    )
    (net (code "120") (name "unconnected-(X1-SPI_CE1-Pad26)") (class "Default")
      (node (ref "X1") (pin "26") (pinfunction "SPI_CE1_26") (pintype "bidirectional"))
    )
    (net (code "121") (name "unconnected-(X1-TXD-Pad8)") (class "Default")
      (node (ref "X1") (pin "8") (pinfunction "TXD_8") (pintype "bidirectional"))
    )
  )
)
